# 6-pin_SOT-23.net
KiCad netlist of a schematic drawn in EAGLE
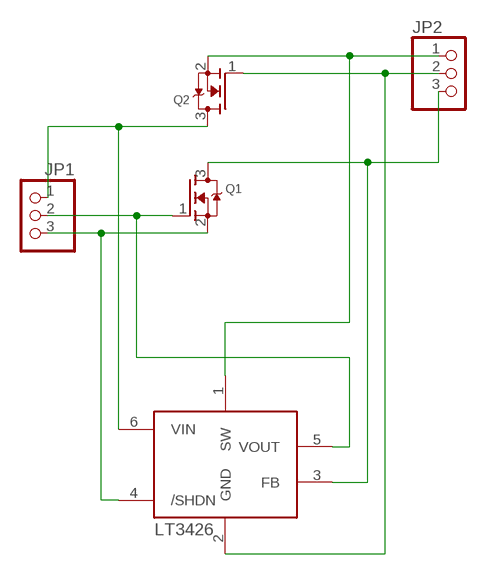
[diagram p0: schematic, sheet 1]

(export (version "E")
  (design (tool "Eeschema 10.0.6"))
  (components
    (comp (ref "JP1")
      (value "PINHD-1X3CB")
      (footprint "eagle-import:1X03-CLEANBIG")
      (libsource (lib "eagle-import") (part "PINHD-1X3CB"))
    )
    (comp (ref "JP2")
      (value "PINHD-1X3CB")
      (footprint "eagle-import:1X03-CLEANBIG")
      (libsource (lib "eagle-import") (part "PINHD-1X3CB"))
    )
    (comp (ref "Q1")
      (value "MOSFET-NREFLOW")
      (footprint "eagle-import:SOT23")
      (libsource (lib "eagle-import") (part "MOSFET-NREFLOW"))
    )
    (comp (ref "Q2")
      (value "MOSFET-NREFLOW")
      (footprint "eagle-import:SOT23")
      (libsource (lib "eagle-import") (part "MOSFET-NREFLOW"))
    )
    (comp (ref "U$1")
      (value "LT3426")
      (footprint "eagle-import:SOT23-6")
      (libsource (lib "eagle-import") (part "LT3426"))
    )
  )
  (nets
    (net (code "1") (name "Net-(Q1-D)") (class "Default")
      (node (ref "JP2") (pin "3") (pinfunction "3_3") (pintype "passive"))
      (node (ref "Q1") (pin "3") (pinfunction "D_3") (pintype "bidirectional"))
      (node (ref "U$1") (pin "3") (pinfunction "FB_3") (pintype "input"))
    )
    (net (code "2") (name "Net-(Q1-G)") (class "Default")
      (node (ref "JP1") (pin "2") (pinfunction "2_2") (pintype "passive"))
      (node (ref "Q1") (pin "1") (pinfunction "G_1") (pintype "bidirectional"))
      (node (ref "U$1") (pin "5") (pinfunction "VOUT_5") (pintype "output"))
    )
    (net (code "3") (name "Net-(Q1-S)") (class "Default")
      (node (ref "JP1") (pin "3") (pinfunction "3_3") (pintype "passive"))
      (node (ref "Q1") (pin "2") (pinfunction "S_2") (pintype "bidirectional"))
      (node (ref "U$1") (pin "4") (pinfunction "/SHDN_4") (pintype "input"))
    )
    (net (code "4") (name "Net-(Q2-D)") (class "Default")
      (node (ref "JP1") (pin "1") (pinfunction "1_1") (pintype "passive"))
      (node (ref "Q2") (pin "3") (pinfunction "D_3") (pintype "bidirectional"))
      (node (ref "U$1") (pin "6") (pinfunction "VIN_6") (pintype "input"))
    )
    (net (code "5") (name "Net-(Q2-G)") (class "Default")
      (node (ref "JP2") (pin "2") (pinfunction "2_2") (pintype "passive"))
      (node (ref "Q2") (pin "1") (pinfunction "G_1") (pintype "bidirectional"))
      (node (ref "U$1") (pin "2") (pinfunction "GND_2") (pintype "power_in"))
    )
    (net (code "6") (name "Net-(Q2-S)") (class "Default")
      (node (ref "JP2") (pin "1") (pinfunction "1_1") (pintype "passive"))
      (node (ref "Q2") (pin "2") (pinfunction "S_2") (pintype "bidirectional"))
      (node (ref "U$1") (pin "1") (pinfunction "SW_1") (pintype "output"))
    )
  )
)
